# sensors-digital.net
KiCad netlist of a schematic drawn in Altium Designer
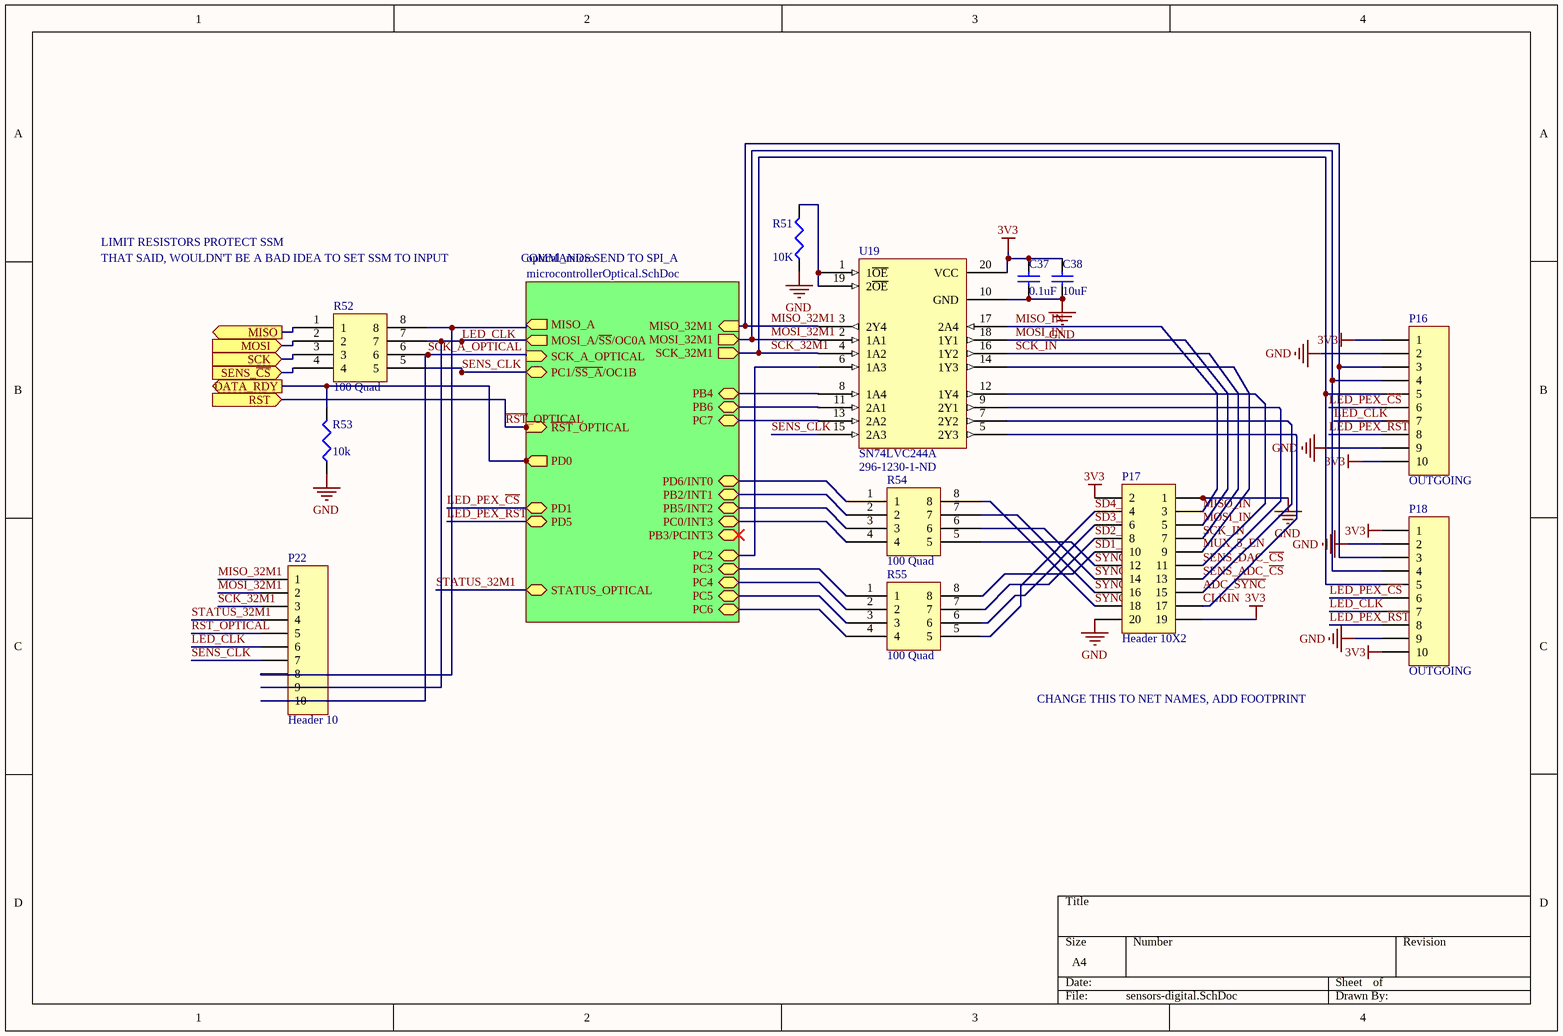
[diagram p0: sensors-digital.SchDoc]

(export (version "E")
  (design (tool "Eeschema 10.0.6"))
  (components
    (comp (ref "C37")
      (value "0.1uF")
      (footprint "1608[0603]")
      (description "Capacitor (Semiconductor SIM Model)")
      (fields (field (name "PUBLISHER") "Altium Limited"))
      (libsource (lib "Miscellaneous Devices") (part "Cap Semi"))
    )
    (comp (ref "C38")
      (value "10uF")
      (footprint "1608[0603]")
      (description "Capacitor (Semiconductor SIM Model)")
      (fields (field (name "PUBLISHER") "Altium Limited"))
      (libsource (lib "Miscellaneous Devices") (part "Cap Semi"))
    )
    (comp (ref "P16")
      (value "OUTGOING")
      (footprint "DF14-10P-1.25H(55)")
      (description "Header, 10-Pin")
      (fields (field (name "PUBLISHER") "Altium Limited"))
      (libsource (lib "Miscellaneous Connectors") (part "Header 10"))
    )
    (comp (ref "P17")
      (value "Header 10X2")
      (footprint "CON20_2X10_Female")
      (description "Header, 10-Pin, Dual row")
      (fields (field (name "PUBLISHER") "Altium Limited"))
      (libsource (lib "Miscellaneous Connectors") (part "Header 10X2"))
    )
    (comp (ref "P18")
      (value "OUTGOING")
      (footprint "DF14-10P-1.25H(55)")
      (description "Header, 10-Pin")
      (fields (field (name "PUBLISHER") "Altium Limited"))
      (libsource (lib "Miscellaneous Connectors") (part "Header 10"))
    )
    (comp (ref "P22")
      (value "Header 10")
      (footprint "HDR1X10")
      (description "Header, 10-Pin")
      (fields (field (name "PUBLISHER") "Altium Limited"))
      (libsource (lib "Miscellaneous Connectors") (part "Header 10"))
    )
    (comp (ref "R51")
      (value "10K")
      (footprint "J1-0603")
      (description "Resistor")
      (fields (field (name "PUBLISHER") "Altium Limited"))
      (libsource (lib "Miscellaneous Devices") (part "Res3"))
    )
    (comp (ref "R52")
      (value "100 Quad")
      (footprint "ResQuad-320X150")
      (description "Quad pack resistor")
      (libsource (lib "PAY") (part "Res Quad Pack"))
    )
    (comp (ref "R53")
      (value "10k")
      (footprint "J1-0603")
      (description "Resistor")
      (fields (field (name "PUBLISHER") "Altium Limited"))
      (libsource (lib "Miscellaneous Devices") (part "Res3"))
    )
    (comp (ref "R54")
      (value "100 Quad")
      (footprint "ResQuad-320X150")
      (description "Quad pack resistor")
      (libsource (lib "PAY") (part "Res Quad Pack"))
    )
    (comp (ref "R55")
      (value "100 Quad")
      (footprint "ResQuad-320X150")
      (description "Quad pack resistor")
      (libsource (lib "PAY") (part "Res Quad Pack"))
    )
    (comp (ref "U19")
      (value "SN74LVC244A")
      (footprint "SOP65P650X440-20N")
      (description "Octal buffer or driver with 3-state outputs.")
      (fields (field (name "SUPPLIER PART NUMBER 1") "296-1230-1-ND"))
      (libsource (lib "ICs") (part "SN74LVC244A"))
    )
  )
  (nets
    (net (code "1") (name "/ADC_~{SYNC}") (class "Default")
      (node (ref "P17") (pin "15") (pinfunction "15_15") (pintype "passive"))
      (node (ref "U19") (pin "7") (pinfunction "2Y2_7") (pintype "output"))
    )
    (net (code "2") (name "/CLKIN") (class "Default")
      (node (ref "P17") (pin "17") (pinfunction "17_17") (pintype "passive"))
      (node (ref "U19") (pin "5") (pinfunction "2Y3_5") (pintype "output"))
    )
    (net (code "3") (name "/DATA_RDY") (class "Default")
      (node (ref "R53") (pin "2") (pinfunction "2_2") (pintype "passive"))
    )
    (net (code "4") (name "/LED_CLK") (class "Default")
      (node (ref "P16") (pin "7") (pinfunction "7_7") (pintype "passive"))
      (node (ref "P18") (pin "7") (pinfunction "7_7") (pintype "passive"))
      (node (ref "P22") (pin "6") (pinfunction "6_6") (pintype "passive"))
      (node (ref "P22") (pin "9") (pinfunction "9_9") (pintype "passive"))
      (node (ref "R52") (pin "7") (pinfunction "7_7") (pintype "passive"))
    )
    (net (code "5") (name "/LED_PEX_~{CS}") (class "Default")
      (node (ref "P16") (pin "6") (pinfunction "6_6") (pintype "passive"))
      (node (ref "P18") (pin "6") (pinfunction "6_6") (pintype "passive"))
    )
    (net (code "6") (name "/LED_PEX_~{RST}") (class "Default")
      (node (ref "P16") (pin "8") (pinfunction "8_8") (pintype "passive"))
      (node (ref "P18") (pin "8") (pinfunction "8_8") (pintype "passive"))
    )
    (net (code "7") (name "/MISO") (class "Default")
      (node (ref "R52") (pin "1") (pinfunction "1_1") (pintype "passive"))
    )
    (net (code "8") (name "/MISO_32M1") (class "Default")
      (node (ref "P16") (pin "3") (pinfunction "3_3") (pintype "passive"))
      (node (ref "P18") (pin "3") (pinfunction "3_3") (pintype "passive"))
      (node (ref "P22") (pin "1") (pinfunction "1_1") (pintype "passive"))
      (node (ref "U19") (pin "3") (pinfunction "2Y4_3") (pintype "output"))
    )
    (net (code "9") (name "/MISO_A") (class "Default")
      (node (ref "P22") (pin "8") (pinfunction "8_8") (pintype "passive"))
      (node (ref "R52") (pin "8") (pinfunction "8_8") (pintype "passive"))
    )
    (net (code "10") (name "/MISO_IN") (class "Default")
      (node (ref "P17") (pin "3") (pinfunction "3_3") (pintype "passive"))
      (node (ref "U19") (pin "17") (pinfunction "2A4_17") (pintype "input"))
    )
    (net (code "11") (name "/MOSI") (class "Default")
      (node (ref "R52") (pin "2") (pinfunction "2_2") (pintype "passive"))
    )
    (net (code "12") (name "/MOSI_32M1") (class "Default")
      (node (ref "P16") (pin "4") (pinfunction "4_4") (pintype "passive"))
      (node (ref "P18") (pin "4") (pinfunction "4_4") (pintype "passive"))
      (node (ref "P22") (pin "2") (pinfunction "2_2") (pintype "passive"))
      (node (ref "U19") (pin "2") (pinfunction "1A1_2") (pintype "input"))
    )
    (net (code "13") (name "/MOSI_IN") (class "Default")
      (node (ref "P17") (pin "5") (pinfunction "5_5") (pintype "passive"))
      (node (ref "U19") (pin "18") (pinfunction "1Y1_18") (pintype "output"))
    )
    (net (code "14") (name "/MUX_5_EN") (class "Default")
      (node (ref "P17") (pin "9") (pinfunction "9_9") (pintype "passive"))
      (node (ref "U19") (pin "14") (pinfunction "1Y3_14") (pintype "output"))
    )
    (net (code "15") (name "/PB2{slash}INT1") (class "Default")
      (node (ref "R54") (pin "2") (pinfunction "2_2") (pintype "passive"))
    )
    (net (code "17") (name "/PB4") (class "Default")
      (node (ref "U19") (pin "8") (pinfunction "1A4_8") (pintype "input"))
    )
    (net (code "18") (name "/PB5{slash}INT2") (class "Default")
      (node (ref "R54") (pin "3") (pinfunction "3_3") (pintype "passive"))
    )
    (net (code "19") (name "/PB6") (class "Default")
      (node (ref "U19") (pin "11") (pinfunction "2A1_11") (pintype "input"))
    )
    (net (code "20") (name "/PC0{slash}INT3") (class "Default")
      (node (ref "R54") (pin "4") (pinfunction "4_4") (pintype "passive"))
    )
    (net (code "21") (name "/PC2") (class "Default")
      (node (ref "U19") (pin "6") (pinfunction "1A3_6") (pintype "input"))
    )
    (net (code "22") (name "/PC3") (class "Default")
      (node (ref "R55") (pin "1") (pinfunction "1_1") (pintype "passive"))
    )
    (net (code "23") (name "/PC4") (class "Default")
      (node (ref "R55") (pin "2") (pinfunction "2_2") (pintype "passive"))
    )
    (net (code "24") (name "/PC5") (class "Default")
      (node (ref "R55") (pin "3") (pinfunction "3_3") (pintype "passive"))
    )
    (net (code "25") (name "/PC6") (class "Default")
      (node (ref "R55") (pin "4") (pinfunction "4_4") (pintype "passive"))
    )
    (net (code "26") (name "/PC7") (class "Default")
      (node (ref "U19") (pin "13") (pinfunction "2A2_13") (pintype "input"))
    )
    (net (code "27") (name "/PD6{slash}INT0") (class "Default")
      (node (ref "R54") (pin "1") (pinfunction "1_1") (pintype "passive"))
    )
    (net (code "28") (name "/SCK") (class "Default")
      (node (ref "R52") (pin "3") (pinfunction "3_3") (pintype "passive"))
    )
    (net (code "29") (name "/SCK_32M1") (class "Default")
      (node (ref "P16") (pin "5") (pinfunction "5_5") (pintype "passive"))
      (node (ref "P18") (pin "5") (pinfunction "5_5") (pintype "passive"))
      (node (ref "P22") (pin "3") (pinfunction "3_3") (pintype "passive"))
      (node (ref "U19") (pin "4") (pinfunction "1A2_4") (pintype "input"))
    )
    (net (code "30") (name "/SCK_A_OPTICAL") (class "Default")
      (node (ref "P22") (pin "10") (pinfunction "10_10") (pintype "passive"))
      (node (ref "R52") (pin "6") (pinfunction "6_6") (pintype "passive"))
    )
    (net (code "31") (name "/SCK_IN") (class "Default")
      (node (ref "P17") (pin "7") (pinfunction "7_7") (pintype "passive"))
      (node (ref "U19") (pin "16") (pinfunction "1Y2_16") (pintype "output"))
    )
    (net (code "32") (name "/SD1_~{CS}") (class "Default")
      (node (ref "P17") (pin "10") (pinfunction "10_10") (pintype "passive"))
      (node (ref "R55") (pin "8") (pinfunction "8_8") (pintype "passive"))
    )
    (net (code "33") (name "/SD2_~{CS}") (class "Default")
      (node (ref "P17") (pin "8") (pinfunction "8_8") (pintype "passive"))
      (node (ref "R55") (pin "7") (pinfunction "7_7") (pintype "passive"))
    )
    (net (code "34") (name "/SD3_~{CS}") (class "Default")
      (node (ref "P17") (pin "6") (pinfunction "6_6") (pintype "passive"))
      (node (ref "R55") (pin "6") (pinfunction "6_6") (pintype "passive"))
    )
    (net (code "35") (name "/SD4_~{CS}") (class "Default")
      (node (ref "P17") (pin "4") (pinfunction "4_4") (pintype "passive"))
      (node (ref "R55") (pin "5") (pinfunction "5_5") (pintype "passive"))
    )
    (net (code "36") (name "/SENS_ADC_~{CS}") (class "Default")
      (node (ref "P17") (pin "13") (pinfunction "13_13") (pintype "passive"))
      (node (ref "U19") (pin "9") (pinfunction "2Y1_9") (pintype "output"))
    )
    (net (code "37") (name "/SENS_CLK") (class "Default")
      (node (ref "P22") (pin "7") (pinfunction "7_7") (pintype "passive"))
      (node (ref "R52") (pin "5") (pinfunction "5_5") (pintype "passive"))
      (node (ref "U19") (pin "15") (pinfunction "2A3_15") (pintype "input"))
    )
    (net (code "38") (name "/SENS_DAC_~{CS}") (class "Default")
      (node (ref "P17") (pin "11") (pinfunction "11_11") (pintype "passive"))
      (node (ref "U19") (pin "12") (pinfunction "1Y4_12") (pintype "output"))
    )
    (net (code "39") (name "/SENS_~{CS}") (class "Default")
      (node (ref "R52") (pin "4") (pinfunction "4_4") (pintype "passive"))
    )
    (net (code "40") (name "/STATUS_32M1") (class "Default")
      (node (ref "P22") (pin "4") (pinfunction "4_4") (pintype "passive"))
    )
    (net (code "41") (name "/SYNCO1") (class "Default")
      (node (ref "P17") (pin "18") (pinfunction "18_18") (pintype "passive"))
      (node (ref "R54") (pin "8") (pinfunction "8_8") (pintype "passive"))
    )
    (net (code "42") (name "/SYNCO2") (class "Default")
      (node (ref "P17") (pin "16") (pinfunction "16_16") (pintype "passive"))
      (node (ref "R54") (pin "7") (pinfunction "7_7") (pintype "passive"))
    )
    (net (code "43") (name "/SYNCO3") (class "Default")
      (node (ref "P17") (pin "14") (pinfunction "14_14") (pintype "passive"))
      (node (ref "R54") (pin "6") (pinfunction "6_6") (pintype "passive"))
    )
    (net (code "44") (name "/SYNCO4") (class "Default")
      (node (ref "P17") (pin "12") (pinfunction "12_12") (pintype "passive"))
      (node (ref "R54") (pin "5") (pinfunction "5_5") (pintype "passive"))
    )
    (net (code "45") (name "/~{RST}_OPTICAL") (class "Default")
      (node (ref "P22") (pin "5") (pinfunction "5_5") (pintype "passive"))
    )
    (net (code "46") (name "3V3") (class "Default")
      (node (ref "C37") (pin "2") (pinfunction "2_2") (pintype "passive"))
      (node (ref "C38") (pin "2") (pinfunction "2_2") (pintype "passive"))
      (node (ref "P16") (pin "1") (pinfunction "1_1") (pintype "passive"))
      (node (ref "P16") (pin "10") (pinfunction "10_10") (pintype "passive"))
      (node (ref "P17") (pin "19") (pinfunction "19_19") (pintype "passive"))
      (node (ref "P17") (pin "2") (pinfunction "2_2") (pintype "passive"))
      (node (ref "P18") (pin "1") (pinfunction "1_1") (pintype "passive"))
      (node (ref "P18") (pin "10") (pinfunction "10_10") (pintype "passive"))
      (node (ref "U19") (pin "20") (pinfunction "VCC_20") (pintype "power_in"))
    )
    (net (code "47") (name "GND") (class "Default")
      (node (ref "C37") (pin "1") (pinfunction "1_1") (pintype "passive"))
      (node (ref "C38") (pin "1") (pinfunction "1_1") (pintype "passive"))
      (node (ref "P16") (pin "2") (pinfunction "2_2") (pintype "passive"))
      (node (ref "P16") (pin "9") (pinfunction "9_9") (pintype "passive"))
      (node (ref "P17") (pin "1") (pinfunction "1_1") (pintype "passive"))
      (node (ref "P17") (pin "20") (pinfunction "20_20") (pintype "passive"))
      (node (ref "P18") (pin "2") (pinfunction "2_2") (pintype "passive"))
      (node (ref "P18") (pin "9") (pinfunction "9_9") (pintype "passive"))
      (node (ref "R51") (pin "1") (pinfunction "1_1") (pintype "passive"))
      (node (ref "R53") (pin "1") (pinfunction "1_1") (pintype "passive"))
      (node (ref "U19") (pin "10") (pinfunction "GND_10") (pintype "power_in"))
    )
    (net (code "48") (name "Net-(U19-1~{OE})") (class "Default")
      (node (ref "R51") (pin "2") (pinfunction "2_2") (pintype "passive"))
      (node (ref "U19") (pin "1") (pinfunction "1~{OE}_1") (pintype "input"))
      (node (ref "U19") (pin "19") (pinfunction "2~{OE}_19") (pintype "input"))
    )
  )
)
